# POWER.net
KiCad netlist of a schematic drawn in Altium Designer
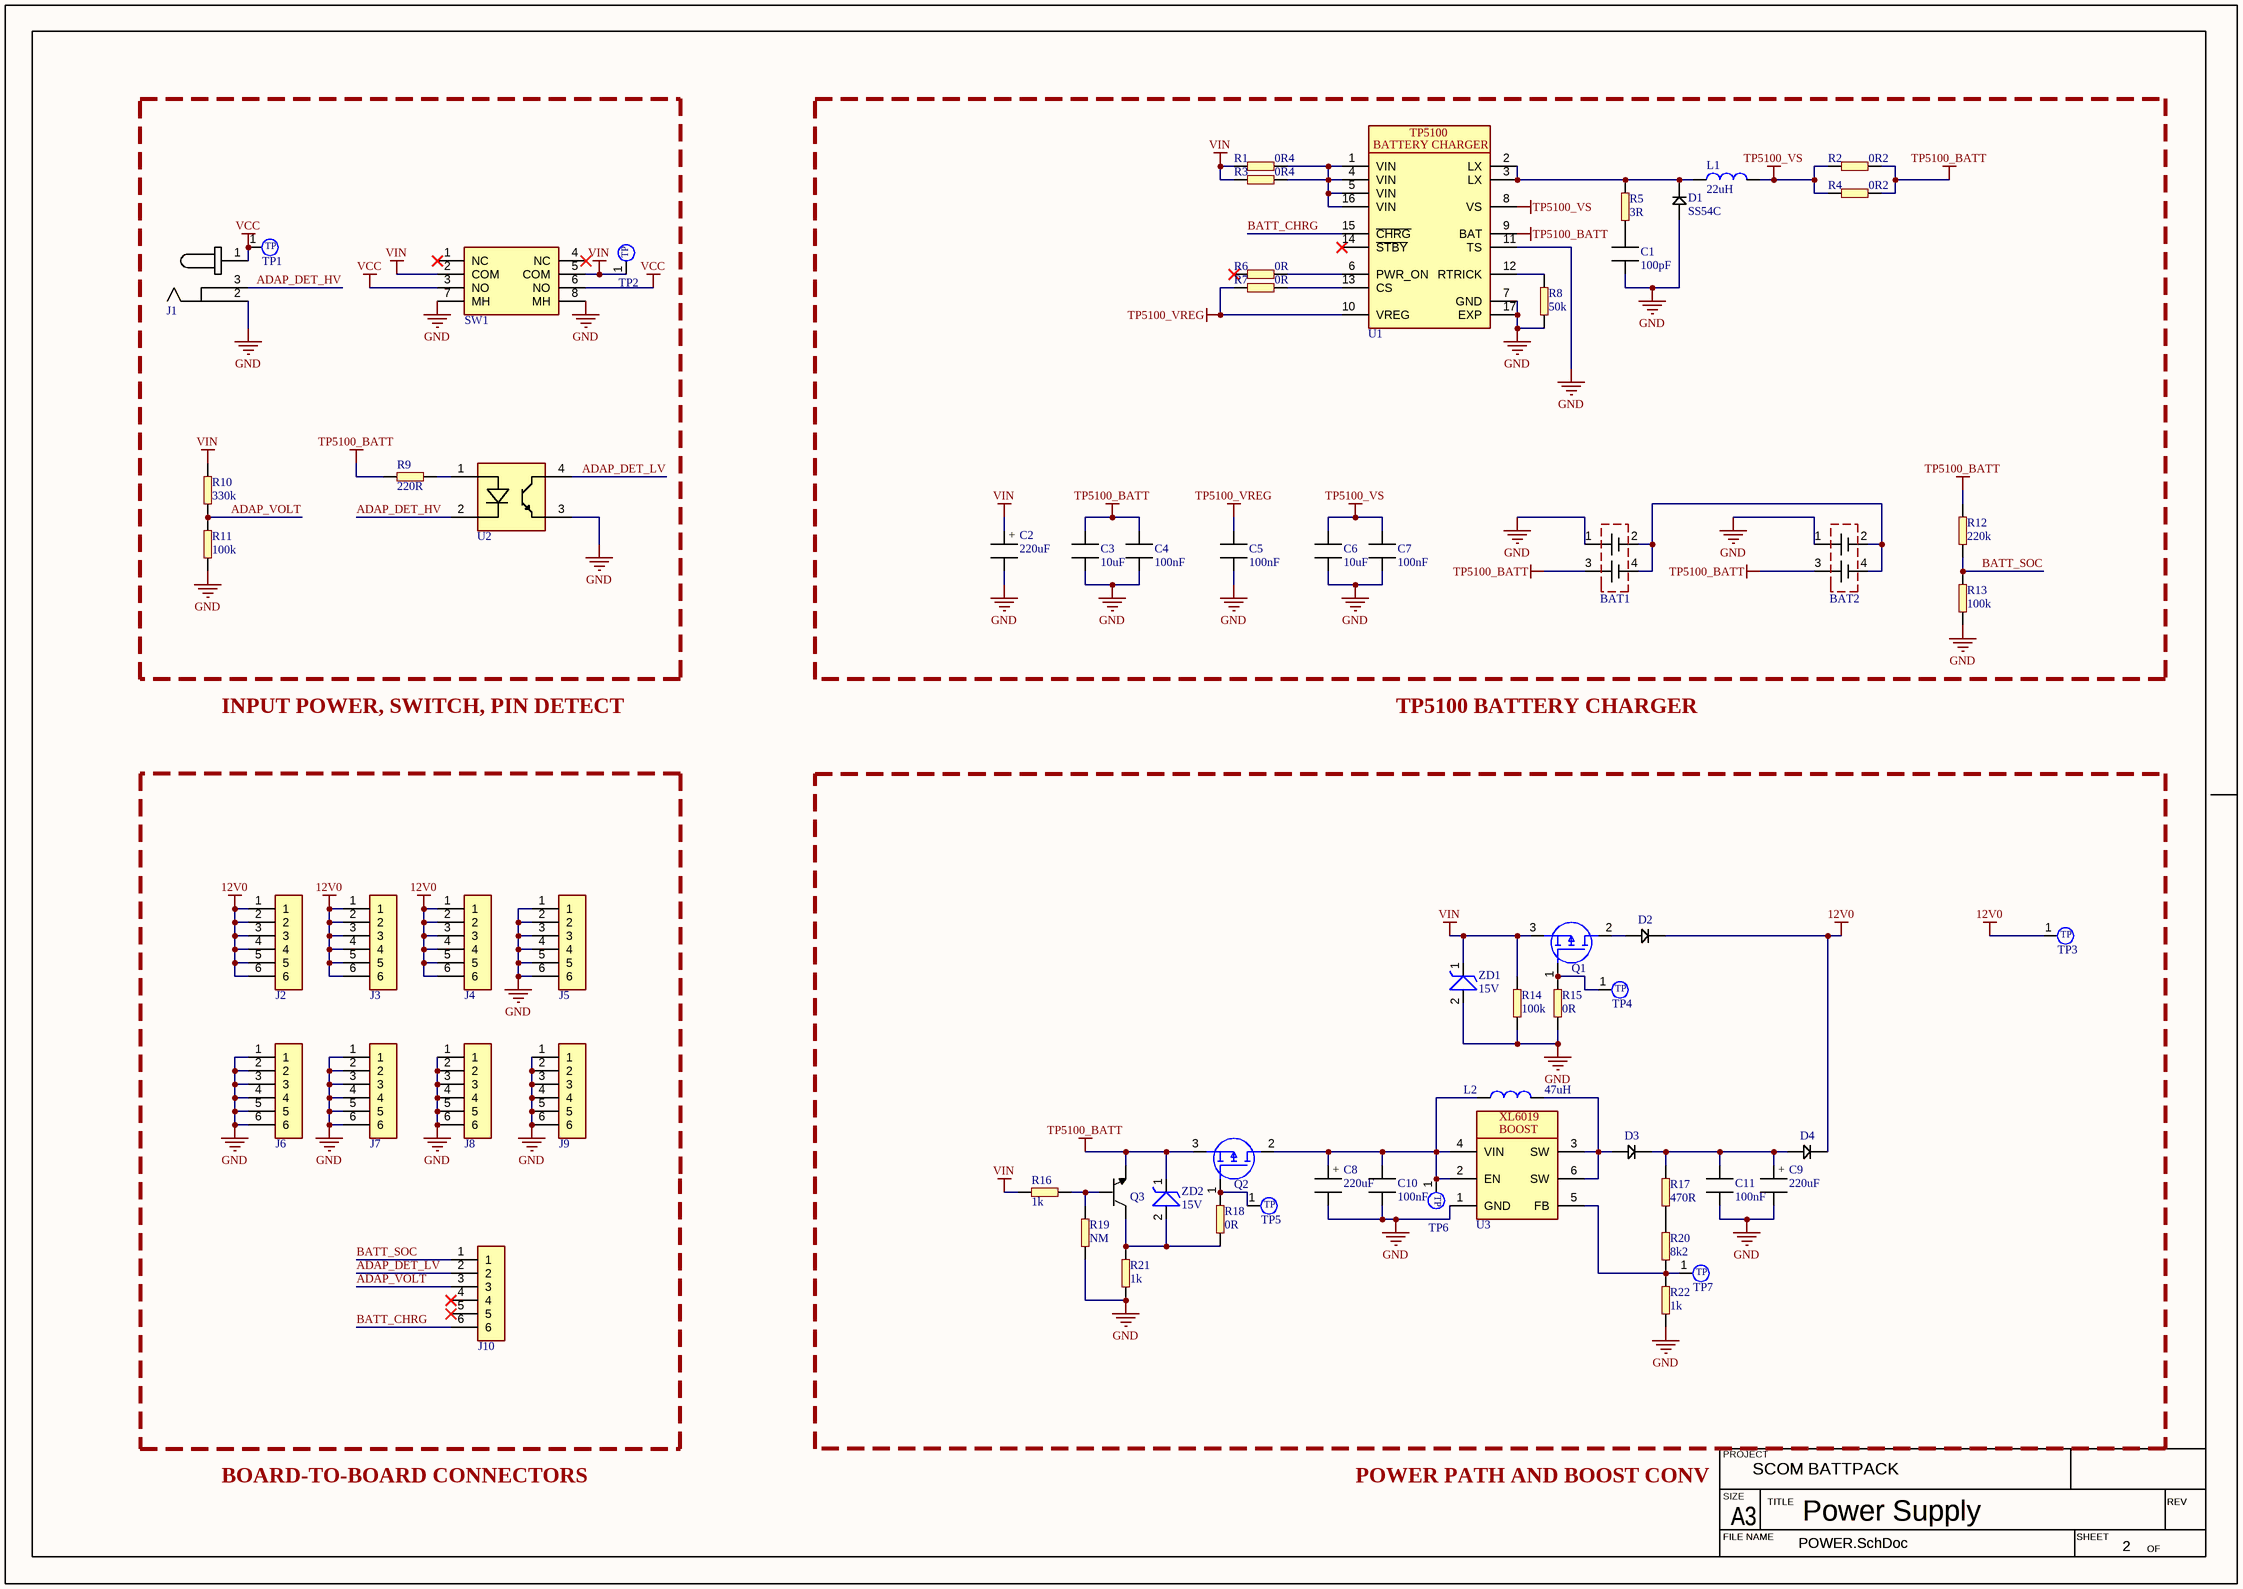
[diagram p0: POWER.SchDoc]

(export (version "E")
  (design (tool "Eeschema 10.0.6"))
  (components
    (comp (ref "BAT1")
      (value "BK-18650-PC4")
      (footprint "BK-18650-PC4")
      (description "BATT HOLDER 18650 2 CELL PC PIN")
      (libsource (lib "Connectors") (part "BK-18650-PC4"))
    )
    (comp (ref "BAT2")
      (value "BK-18650-PC4")
      (footprint "BK-18650-PC4")
      (description "BATT HOLDER 18650 2 CELL PC PIN")
      (libsource (lib "Connectors") (part "BK-18650-PC4"))
    )
    (comp (ref "C1")
      (value "100pF")
      (footprint "CAPC2012X13L")
      (description "Chip Capacitor, 2-Leads, Body 2.00x1.25mm, IPC High Density")
      (fields (field (name "Comment") "MLCC_0805"))
      (libsource (lib "Capacitor") (part "MLCC_0805"))
    )
    (comp (ref "C2")
      (value "220uF")
      (footprint "CAP_6.3_7.7")
      (description "Electrolytic Capacitor SMD 6.3x7.7")
      (fields (field (name "Comment") "ERP_102-2"))
      (libsource (lib "ElectrolyticCapacitor") (part "CAP_6.3_7.7"))
    )
    (comp (ref "C3")
      (value "10uF")
      (footprint "CAPC2012X13L")
      (description "Chip Capacitor, 2-Leads, Body 2.00x1.25mm, IPC High Density")
      (fields (field (name "Comment") "MLCC_0805"))
      (libsource (lib "Capacitor") (part "MLCC_0805"))
    )
    (comp (ref "C4")
      (value "100nF")
      (footprint "CAPC2012X13L")
      (description "Chip Capacitor, 2-Leads, Body 2.00x1.25mm, IPC High Density")
      (fields (field (name "Comment") "MLCC_0805"))
      (libsource (lib "Capacitor") (part "MLCC_0805"))
    )
    (comp (ref "C5")
      (value "100nF")
      (footprint "CAPC2012X13L")
      (description "Chip Capacitor, 2-Leads, Body 2.00x1.25mm, IPC High Density")
      (fields (field (name "Comment") "MLCC_0805"))
      (libsource (lib "Capacitor") (part "MLCC_0805"))
    )
    (comp (ref "C6")
      (value "10uF")
      (footprint "CAPC2012X13L")
      (description "Chip Capacitor, 2-Leads, Body 2.00x1.25mm, IPC High Density")
      (fields (field (name "Comment") "MLCC_0805"))
      (libsource (lib "Capacitor") (part "MLCC_0805"))
    )
    (comp (ref "C7")
      (value "100nF")
      (footprint "CAPC2012X13L")
      (description "Chip Capacitor, 2-Leads, Body 2.00x1.25mm, IPC High Density")
      (fields (field (name "Comment") "MLCC_0805"))
      (libsource (lib "Capacitor") (part "MLCC_0805"))
    )
    (comp (ref "C8")
      (value "220uF")
      (footprint "CAP_6.3_7.7")
      (description "Electrolytic Capacitor SMD 6.3x7.7")
      (fields (field (name "Comment") "ERP_102-2"))
      (libsource (lib "ElectrolyticCapacitor") (part "CAP_6.3_7.7"))
    )
    (comp (ref "C9")
      (value "220uF")
      (footprint "CAP_6.3_7.7")
      (description "Electrolytic Capacitor SMD 6.3x7.7")
      (fields (field (name "Comment") "ERP_102-2"))
      (libsource (lib "ElectrolyticCapacitor") (part "CAP_6.3_7.7"))
    )
    (comp (ref "C10")
      (value "100nF")
      (footprint "CAPC2012X13L")
      (description "Chip Capacitor, 2-Leads, Body 2.00x1.25mm, IPC High Density")
      (fields (field (name "Comment") "MLCC_0805"))
      (libsource (lib "Capacitor") (part "MLCC_0805"))
    )
    (comp (ref "C11")
      (value "100nF")
      (footprint "CAPC2012X13L")
      (description "Chip Capacitor, 2-Leads, Body 2.00x1.25mm, IPC High Density")
      (fields (field (name "Comment") "MLCC_0805"))
      (libsource (lib "Capacitor") (part "MLCC_0805"))
    )
    (comp (ref "D1")
      (value "SS54C")
      (footprint "DIOM6959X26L")
      (fields (field (name "Comment") "ERP_104-3"))
      (libsource (lib "Schottky") (part "SS54"))
    )
    (comp (ref "D2")
      (value "ERP_104-3")
      (footprint "DIOM6959X26L")
      (libsource (lib "Schottky") (part "SS54"))
    )
    (comp (ref "D3")
      (value "ERP_104-3")
      (footprint "DIOM6959X26L")
      (libsource (lib "Schottky") (part "SS54"))
    )
    (comp (ref "D4")
      (value "ERP_104-3")
      (footprint "DIOM6959X26L")
      (libsource (lib "Schottky") (part "SS54"))
    )
    (comp (ref "J1")
      (value "KLDX-0202-AC")
      (footprint "KLDX-0202-AC")
      (description "CONN PWR JACK 2X5.5MM KINKED PIN")
      (libsource (lib "Connectors") (part "KLDX-0202-AC"))
    )
    (comp (ref "J2")
      (value "ERP_148-2")
      (footprint "6PX1R_F")
      (description "6PX1R Female Header")
      (libsource (lib "PinHeader") (part "6PX1R_F"))
    )
    (comp (ref "J3")
      (value "ERP_148-2")
      (footprint "6PX1R_F")
      (description "6PX1R Female Header")
      (libsource (lib "PinHeader") (part "6PX1R_F"))
    )
    (comp (ref "J4")
      (value "ERP_148-2")
      (footprint "6PX1R_F")
      (description "6PX1R Female Header")
      (libsource (lib "PinHeader") (part "6PX1R_F"))
    )
    (comp (ref "J5")
      (value "ERP_148-2")
      (footprint "6PX1R_F")
      (description "6PX1R Female Header")
      (libsource (lib "PinHeader") (part "6PX1R_F"))
    )
    (comp (ref "J6")
      (value "ERP_148-2")
      (footprint "6PX1R_F")
      (description "6PX1R Female Header")
      (libsource (lib "PinHeader") (part "6PX1R_F"))
    )
    (comp (ref "J7")
      (value "ERP_148-2")
      (footprint "6PX1R_F")
      (description "6PX1R Female Header")
      (libsource (lib "PinHeader") (part "6PX1R_F"))
    )
    (comp (ref "J8")
      (value "ERP_148-2")
      (footprint "6PX1R_F")
      (description "6PX1R Female Header")
      (libsource (lib "PinHeader") (part "6PX1R_F"))
    )
    (comp (ref "J9")
      (value "ERP_148-2")
      (footprint "6PX1R_F")
      (description "6PX1R Female Header")
      (libsource (lib "PinHeader") (part "6PX1R_F"))
    )
    (comp (ref "J10")
      (value "ERP_148-2")
      (footprint "6PX1R_F")
      (description "6PX1R Female Header")
      (libsource (lib "PinHeader") (part "6PX1R_F"))
    )
    (comp (ref "L1")
      (value "22uH")
      (footprint "IND_1212")
      (description "IND_1212")
      (libsource (lib "Inductor") (part "IND_1212"))
    )
    (comp (ref "L2")
      (value "47uH")
      (footprint "IND_1212")
      (description "IND_1212")
      (libsource (lib "Inductor") (part "IND_1212"))
    )
    (comp (ref "Q1")
      (value "IRFR5305TRPBF")
      (footprint "DPAK229P991X239-3M")
      (description "P Channel MOSFET -55V HEXFET 65mOhms 42nC TO-252-3")
      (libsource (lib "MOSFET") (part "IRFR5305TRPBF"))
    )
    (comp (ref "Q2")
      (value "IRFR5305TRPBF")
      (footprint "DPAK229P991X239-3M")
      (description "P Channel MOSFET -55V HEXFET 65mOhms 42nC TO-252-3")
      (libsource (lib "MOSFET") (part "IRFR5305TRPBF"))
    )
    (comp (ref "Q3")
      (value "ERP_105-1")
      (footprint "MMBT2222")
      (description "MMBT2222A")
      (libsource (lib "BJT") (part "MMBT2222"))
    )
    (comp (ref "R1")
      (value "0R4")
      (footprint "RESC3116X06M")
      (description "RES_1206")
      (libsource (lib "Resistor") (part "RES_1206"))
    )
    (comp (ref "R2")
      (value "0R2")
      (footprint "RESC3116X06M")
      (description "RES_1206")
      (libsource (lib "Resistor") (part "RES_1206"))
    )
    (comp (ref "R3")
      (value "0R4")
      (footprint "RESC3116X06M")
      (description "RES_1206")
      (libsource (lib "Resistor") (part "RES_1206"))
    )
    (comp (ref "R4")
      (value "0R2")
      (footprint "RESC3116X06M")
      (description "RES_1206")
      (libsource (lib "Resistor") (part "RES_1206"))
    )
    (comp (ref "R5")
      (value "3R")
      (footprint "RES_0603")
      (description "RES_0603")
      (fields (field (name "Comment") "ERP_101-1"))
      (libsource (lib "") (part "RES_0603_2"))
    )
    (comp (ref "R6")
      (value "0R")
      (footprint "RES_0603")
      (description "RES_0603")
      (fields (field (name "Comment") "ERP_101-1"))
      (libsource (lib "") (part "RES_0603_1"))
    )
    (comp (ref "R7")
      (value "0R")
      (footprint "RES_0603")
      (description "RES_0603")
      (fields (field (name "Comment") "ERP_101-1"))
      (libsource (lib "") (part "RES_0603_1"))
    )
    (comp (ref "R8")
      (value "50k")
      (footprint "RES_0603")
      (description "RES_0603")
      (fields (field (name "Comment") "ERP_101-1"))
      (libsource (lib "") (part "RES_0603_2"))
    )
    (comp (ref "R9")
      (value "220R")
      (footprint "RES_0603")
      (description "RES_0603")
      (fields (field (name "Comment") "ERP_101-1"))
      (libsource (lib "") (part "RES_0603_1"))
    )
    (comp (ref "R10")
      (value "330k")
      (footprint "RES_0603")
      (description "RES_0603")
      (fields (field (name "Comment") "ERP_101-1"))
      (libsource (lib "") (part "RES_0603_2"))
    )
    (comp (ref "R11")
      (value "100k")
      (footprint "RES_0603")
      (description "RES_0603")
      (fields (field (name "Comment") "ERP_101-1"))
      (libsource (lib "Resistor") (part "RES_0603"))
    )
    (comp (ref "R12")
      (value "220k")
      (footprint "RES_0603")
      (description "RES_0603")
      (fields (field (name "Comment") "ERP_101-1"))
      (libsource (lib "") (part "RES_0603_2"))
    )
    (comp (ref "R13")
      (value "100k")
      (footprint "RES_0603")
      (description "RES_0603")
      (fields (field (name "Comment") "ERP_101-1"))
      (libsource (lib "") (part "RES_0603_2"))
    )
    (comp (ref "R14")
      (value "100k")
      (footprint "RES_0603")
      (description "RES_0603")
      (fields (field (name "Comment") "ERP_101-1"))
      (libsource (lib "") (part "RES_0603_2"))
    )
    (comp (ref "R15")
      (value "0R")
      (footprint "RES_0603")
      (description "RES_0603")
      (fields (field (name "Comment") "ERP_101-1"))
      (libsource (lib "") (part "RES_0603_2"))
    )
    (comp (ref "R16")
      (value "1k")
      (footprint "RES_0603")
      (description "RES_0603")
      (fields (field (name "Comment") "ERP_101-1"))
      (libsource (lib "") (part "RES_0603_3"))
    )
    (comp (ref "R17")
      (value "470R")
      (footprint "RES_0603")
      (description "RES_0603")
      (fields (field (name "Comment") "ERP_101-1"))
      (libsource (lib "Resistor") (part "RES_0603"))
    )
    (comp (ref "R18")
      (value "0R")
      (footprint "RES_0603")
      (description "RES_0603")
      (fields (field (name "Comment") "ERP_101-1"))
      (libsource (lib "") (part "RES_0603_2"))
    )
    (comp (ref "R19")
      (value "NM")
      (footprint "RES_0603")
      (description "RES_0603")
      (fields (field (name "Comment") "ERP_101-1"))
      (libsource (lib "Resistor") (part "RES_0603"))
    )
    (comp (ref "R20")
      (value "8k2")
      (footprint "RES_0603")
      (description "RES_0603")
      (fields (field (name "Comment") "ERP_101-1"))
      (libsource (lib "Resistor") (part "RES_0603"))
    )
    (comp (ref "R21")
      (value "1k")
      (footprint "RES_0603")
      (description "RES_0603")
      (fields (field (name "Comment") "ERP_101-1"))
      (libsource (lib "Resistor") (part "RES_0603"))
    )
    (comp (ref "R22")
      (value "1k")
      (footprint "RES_0603")
      (description "RES_0603")
      (fields (field (name "Comment") "ERP_101-1"))
      (libsource (lib "Resistor") (part "RES_0603"))
    )
    (comp (ref "SW1")
      (value "ERP_110-4")
      (footprint "PBH2U")
      (description "Pushbutton Switch DPDT Standard Through Hole, Right Angle")
      (libsource (lib "Switch") (part "PBH2U"))
    )
    (comp (ref "TP1") (value "TP_1MM") (footprint "TP_1MM") (libsource (lib "Jumper") (part "TP_1MM")))
    (comp (ref "TP2") (value "TP_1MM") (footprint "TP_1MM") (libsource (lib "Jumper") (part "TP_1MM")))
    (comp (ref "TP3") (value "TP_1MM") (footprint "TP_1MM") (libsource (lib "Jumper") (part "TP_1MM")))
    (comp (ref "TP4") (value "TP_1MM") (footprint "TP_1MM") (libsource (lib "Jumper") (part "TP_1MM")))
    (comp (ref "TP5") (value "TP_1MM") (footprint "TP_1MM") (libsource (lib "Jumper") (part "TP_1MM")))
    (comp (ref "TP6") (value "TP_1MM") (footprint "TP_1MM") (libsource (lib "Jumper") (part "TP_1MM")))
    (comp (ref "TP7") (value "TP_1MM") (footprint "TP_1MM") (libsource (lib "Jumper") (part "TP_1MM")))
    (comp (ref "U1")
      (value "TP5100")
      (footprint "QFN65P400X400X90_HS-17M")
      (description "Switching-buck type (double 8.4V / single 4.2V) lithium battery charging management chip")
      (libsource (lib "BatteryCharger") (part "TP5100"))
    )
    (comp (ref "U2")
      (value "FOD817A3SD")
      (footprint "FOD817A3SD")
      (description "OPTOISOLATOR 5KV TRANSISTOR 4SMD")
      (libsource (lib "Optocoupler") (part "FOD817A3SD"))
    )
    (comp (ref "U3")
      (value "XL6019")
      (footprint "DPAK171P1524X483-6M")
      (description "5A 180KHz 32V Boost DC to DC Converter")
      (libsource (lib "DCDC_Switcher") (part "XL6019"))
    )
    (comp (ref "ZD1")
      (value "15V")
      (footprint "SOD323")
      (description "Zener SOD-323 0.3W")
      (fields (field (name "Comment") "MM3Z"))
      (libsource (lib "Zener") (part "MM3Z"))
    )
    (comp (ref "ZD2")
      (value "15V")
      (footprint "SOD323")
      (description "Zener SOD-323 0.3W")
      (fields (field (name "Comment") "MM3Z"))
      (libsource (lib "Zener") (part "MM3Z"))
    )
  )
  (nets
    (net (code "1") (name "/ADAP_DET_HV") (class "Default")
      (node (ref "J1") (pin "3") (pinfunction "3_3") (pintype "passive"))
      (node (ref "U2") (pin "2") (pinfunction "CATHODE_2") (pintype "passive"))
    )
    (net (code "2") (name "/ADAP_DET_LV") (class "Default")
      (node (ref "J10") (pin "2") (pinfunction "2_2") (pintype "passive"))
      (node (ref "U2") (pin "4") (pinfunction "COLLECTOR_4") (pintype "passive"))
    )
    (net (code "3") (name "/ADAP_VOLT") (class "Default")
      (node (ref "J10") (pin "3") (pinfunction "3_3") (pintype "passive"))
      (node (ref "R10") (pin "1") (pinfunction "1_1") (pintype "passive"))
      (node (ref "R11") (pin "1") (pinfunction "1_1") (pintype "passive"))
    )
    (net (code "4") (name "/BATT_CHRG") (class "Default")
      (node (ref "J10") (pin "6") (pinfunction "6_6") (pintype "passive"))
      (node (ref "U1") (pin "15") (pinfunction "~{CHRG}_15") (pintype "passive"))
    )
    (net (code "5") (name "/BATT_SOC") (class "Default")
      (node (ref "J10") (pin "1") (pinfunction "1_1") (pintype "passive"))
      (node (ref "R12") (pin "1") (pinfunction "1_1") (pintype "passive"))
      (node (ref "R13") (pin "2") (pinfunction "2_2") (pintype "passive"))
    )
    (net (code "6") (name "12V0") (class "Default")
      (node (ref "D2") (pin "1") (pinfunction "C_1") (pintype "passive"))
      (node (ref "D4") (pin "1") (pinfunction "C_1") (pintype "passive"))
      (node (ref "J2") (pin "1") (pinfunction "1_1") (pintype "passive"))
      (node (ref "J2") (pin "2") (pinfunction "2_2") (pintype "passive"))
      (node (ref "J2") (pin "3") (pinfunction "3_3") (pintype "passive"))
      (node (ref "J2") (pin "4") (pinfunction "4_4") (pintype "passive"))
      (node (ref "J2") (pin "5") (pinfunction "5_5") (pintype "passive"))
      (node (ref "J2") (pin "6") (pinfunction "6_6") (pintype "passive"))
      (node (ref "J3") (pin "1") (pinfunction "1_1") (pintype "passive"))
      (node (ref "J3") (pin "2") (pinfunction "2_2") (pintype "passive"))
      (node (ref "J3") (pin "3") (pinfunction "3_3") (pintype "passive"))
      (node (ref "J3") (pin "4") (pinfunction "4_4") (pintype "passive"))
      (node (ref "J3") (pin "5") (pinfunction "5_5") (pintype "passive"))
      (node (ref "J3") (pin "6") (pinfunction "6_6") (pintype "passive"))
      (node (ref "J4") (pin "1") (pinfunction "1_1") (pintype "passive"))
      (node (ref "J4") (pin "2") (pinfunction "2_2") (pintype "passive"))
      (node (ref "J4") (pin "3") (pinfunction "3_3") (pintype "passive"))
      (node (ref "J4") (pin "4") (pinfunction "4_4") (pintype "passive"))
      (node (ref "J4") (pin "5") (pinfunction "5_5") (pintype "passive"))
      (node (ref "J4") (pin "6") (pinfunction "6_6") (pintype "passive"))
      (node (ref "TP3") (pin "1") (pinfunction "1_1") (pintype "passive"))
    )
    (net (code "7") (name "GND") (class "Default")
      (node (ref "BAT1") (pin "1") (pinfunction "+_1") (pintype "passive"))
      (node (ref "BAT2") (pin "1") (pinfunction "+_1") (pintype "passive"))
      (node (ref "C1") (pin "2") (pinfunction "2_2") (pintype "passive"))
      (node (ref "C10") (pin "2") (pinfunction "2_2") (pintype "passive"))
      (node (ref "C11") (pin "2") (pinfunction "2_2") (pintype "passive"))
      (node (ref "C2") (pin "2") (pinfunction "2_2") (pintype "passive"))
      (node (ref "C3") (pin "2") (pinfunction "2_2") (pintype "passive"))
      (node (ref "C4") (pin "2") (pinfunction "2_2") (pintype "passive"))
      (node (ref "C5") (pin "2") (pinfunction "2_2") (pintype "passive"))
      (node (ref "C6") (pin "2") (pinfunction "2_2") (pintype "passive"))
      (node (ref "C7") (pin "2") (pinfunction "2_2") (pintype "passive"))
      (node (ref "C8") (pin "2") (pinfunction "2_2") (pintype "passive"))
      (node (ref "C9") (pin "2") (pinfunction "2_2") (pintype "passive"))
      (node (ref "D1") (pin "2") (pinfunction "A_2") (pintype "passive"))
      (node (ref "J1") (pin "2") (pinfunction "2_2") (pintype "passive"))
      (node (ref "J5") (pin "1") (pinfunction "1_1") (pintype "passive"))
      (node (ref "J5") (pin "2") (pinfunction "2_2") (pintype "passive"))
      (node (ref "J5") (pin "3") (pinfunction "3_3") (pintype "passive"))
      (node (ref "J5") (pin "4") (pinfunction "4_4") (pintype "passive"))
      (node (ref "J5") (pin "5") (pinfunction "5_5") (pintype "passive"))
      (node (ref "J5") (pin "6") (pinfunction "6_6") (pintype "passive"))
      (node (ref "J6") (pin "1") (pinfunction "1_1") (pintype "passive"))
      (node (ref "J6") (pin "2") (pinfunction "2_2") (pintype "passive"))
      (node (ref "J6") (pin "3") (pinfunction "3_3") (pintype "passive"))
      (node (ref "J6") (pin "4") (pinfunction "4_4") (pintype "passive"))
      (node (ref "J6") (pin "5") (pinfunction "5_5") (pintype "passive"))
      (node (ref "J6") (pin "6") (pinfunction "6_6") (pintype "passive"))
      (node (ref "J7") (pin "1") (pinfunction "1_1") (pintype "passive"))
      (node (ref "J7") (pin "2") (pinfunction "2_2") (pintype "passive"))
      (node (ref "J7") (pin "3") (pinfunction "3_3") (pintype "passive"))
      (node (ref "J7") (pin "4") (pinfunction "4_4") (pintype "passive"))
      (node (ref "J7") (pin "5") (pinfunction "5_5") (pintype "passive"))
      (node (ref "J7") (pin "6") (pinfunction "6_6") (pintype "passive"))
      (node (ref "J8") (pin "1") (pinfunction "1_1") (pintype "passive"))
      (node (ref "J8") (pin "2") (pinfunction "2_2") (pintype "passive"))
      (node (ref "J8") (pin "3") (pinfunction "3_3") (pintype "passive"))
      (node (ref "J8") (pin "4") (pinfunction "4_4") (pintype "passive"))
      (node (ref "J8") (pin "5") (pinfunction "5_5") (pintype "passive"))
      (node (ref "J8") (pin "6") (pinfunction "6_6") (pintype "passive"))
      (node (ref "J9") (pin "1") (pinfunction "1_1") (pintype "passive"))
      (node (ref "J9") (pin "2") (pinfunction "2_2") (pintype "passive"))
      (node (ref "J9") (pin "3") (pinfunction "3_3") (pintype "passive"))
      (node (ref "J9") (pin "4") (pinfunction "4_4") (pintype "passive"))
      (node (ref "J9") (pin "5") (pinfunction "5_5") (pintype "passive"))
      (node (ref "J9") (pin "6") (pinfunction "6_6") (pintype "passive"))
      (node (ref "R11") (pin "2") (pinfunction "2_2") (pintype "passive"))
      (node (ref "R13") (pin "1") (pinfunction "1_1") (pintype "passive"))
      (node (ref "R14") (pin "1") (pinfunction "1_1") (pintype "passive"))
      (node (ref "R15") (pin "1") (pinfunction "1_1") (pintype "passive"))
      (node (ref "R19") (pin "2") (pinfunction "2_2") (pintype "passive"))
      (node (ref "R21") (pin "2") (pinfunction "2_2") (pintype "passive"))
      (node (ref "R22") (pin "2") (pinfunction "2_2") (pintype "passive"))
      (node (ref "R8") (pin "1") (pinfunction "1_1") (pintype "passive"))
      (node (ref "SW1") (pin "7") (pinfunction "MH_7") (pintype "passive"))
      (node (ref "SW1") (pin "8") (pinfunction "MH_8") (pintype "passive"))
      (node (ref "U1") (pin "11") (pinfunction "TS_11") (pintype "passive"))
      (node (ref "U1") (pin "17") (pinfunction "EXP_17") (pintype "passive"))
      (node (ref "U1") (pin "7") (pinfunction "GND_7") (pintype "passive"))
      (node (ref "U2") (pin "3") (pinfunction "EMITTER_3") (pintype "passive"))
      (node (ref "U3") (pin "1") (pinfunction "GND_1") (pintype "passive"))
      (node (ref "ZD1") (pin "2") (pinfunction "A_2") (pintype "passive"))
    )
    (net (code "8") (name "Net-(BAT1---Pad2)") (class "Default")
      (node (ref "BAT1") (pin "2") (pinfunction "-_2") (pintype "passive"))
      (node (ref "BAT1") (pin "4") (pinfunction "-_4") (pintype "passive"))
      (node (ref "BAT2") (pin "2") (pinfunction "-_2") (pintype "passive"))
      (node (ref "BAT2") (pin "4") (pinfunction "-_4") (pintype "passive"))
    )
    (net (code "9") (name "Net-(C1-Pad1)") (class "Default")
      (node (ref "C1") (pin "1") (pinfunction "1_1") (pintype "passive"))
      (node (ref "R5") (pin "1") (pinfunction "1_1") (pintype "passive"))
    )
    (net (code "10") (name "Net-(D1-C)") (class "Default")
      (node (ref "D1") (pin "1") (pinfunction "C_1") (pintype "passive"))
      (node (ref "L1") (pin "1") (pinfunction "1_1") (pintype "passive"))
      (node (ref "R5") (pin "2") (pinfunction "2_2") (pintype "passive"))
      (node (ref "U1") (pin "2") (pinfunction "LX_2") (pintype "passive"))
      (node (ref "U1") (pin "3") (pinfunction "LX_3") (pintype "passive"))
    )
    (net (code "11") (name "Net-(D2-A)") (class "Default")
      (node (ref "D2") (pin "2") (pinfunction "A_2") (pintype "passive"))
      (node (ref "Q1") (pin "2") (pinfunction "D_2") (pintype "passive"))
    )
    (net (code "12") (name "Net-(D3-A)") (class "Default")
      (node (ref "D3") (pin "2") (pinfunction "A_2") (pintype "passive"))
      (node (ref "L2") (pin "2") (pinfunction "2_2") (pintype "passive"))
      (node (ref "U3") (pin "3") (pinfunction "SW_3") (pintype "passive"))
      (node (ref "U3") (pin "6") (pinfunction "SW_6") (pintype "passive"))
    )
    (net (code "13") (name "Net-(D3-C)") (class "Default")
      (node (ref "C11") (pin "1") (pinfunction "1_1") (pintype "passive"))
      (node (ref "C9") (pin "1") (pinfunction "1_1") (pintype "passive"))
      (node (ref "D3") (pin "1") (pinfunction "C_1") (pintype "passive"))
      (node (ref "D4") (pin "2") (pinfunction "A_2") (pintype "passive"))
      (node (ref "R17") (pin "1") (pinfunction "1_1") (pintype "passive"))
    )
    (net (code "14") (name "Net-(Q1-G)") (class "Default")
      (node (ref "Q1") (pin "1") (pinfunction "G_1") (pintype "passive"))
      (node (ref "R15") (pin "2") (pinfunction "2_2") (pintype "passive"))
      (node (ref "TP4") (pin "1") (pinfunction "1_1") (pintype "passive"))
    )
    (net (code "15") (name "Net-(Q2-D)") (class "Default")
      (node (ref "C10") (pin "1") (pinfunction "1_1") (pintype "passive"))
      (node (ref "C8") (pin "1") (pinfunction "1_1") (pintype "passive"))
      (node (ref "L2") (pin "1") (pinfunction "1_1") (pintype "passive"))
      (node (ref "Q2") (pin "2") (pinfunction "D_2") (pintype "passive"))
      (node (ref "TP6") (pin "1") (pinfunction "1_1") (pintype "passive"))
      (node (ref "U3") (pin "2") (pinfunction "EN_2") (pintype "passive"))
      (node (ref "U3") (pin "4") (pinfunction "VIN_4") (pintype "passive"))
    )
    (net (code "16") (name "Net-(Q2-G)") (class "Default")
      (node (ref "Q2") (pin "1") (pinfunction "G_1") (pintype "passive"))
      (node (ref "R18") (pin "2") (pinfunction "2_2") (pintype "passive"))
      (node (ref "TP5") (pin "1") (pinfunction "1_1") (pintype "passive"))
    )
    (net (code "17") (name "Net-(Q3-Pad1)") (class "Default")
      (node (ref "Q3") (pin "1") (pinfunction "1_1") (pintype "passive"))
      (node (ref "R16") (pin "1") (pinfunction "1_1") (pintype "passive"))
      (node (ref "R19") (pin "1") (pinfunction "1_1") (pintype "passive"))
    )
    (net (code "18") (name "Net-(R1-Pad1)") (class "Default")
      (node (ref "R1") (pin "1") (pinfunction "1_1") (pintype "passive"))
      (node (ref "R3") (pin "1") (pinfunction "1_1") (pintype "passive"))
      (node (ref "U1") (pin "1") (pinfunction "VIN_1") (pintype "passive"))
      (node (ref "U1") (pin "16") (pinfunction "VIN_16") (pintype "passive"))
      (node (ref "U1") (pin "4") (pinfunction "VIN_4") (pintype "passive"))
      (node (ref "U1") (pin "5") (pinfunction "VIN_5") (pintype "passive"))
    )
    (net (code "19") (name "Net-(R17-Pad2)") (class "Default")
      (node (ref "R17") (pin "2") (pinfunction "2_2") (pintype "passive"))
      (node (ref "R20") (pin "1") (pinfunction "1_1") (pintype "passive"))
    )
    (net (code "20") (name "Net-(U1-CS)") (class "Default")
      (node (ref "R7") (pin "2") (pinfunction "2_2") (pintype "passive"))
      (node (ref "U1") (pin "13") (pinfunction "CS_13") (pintype "passive"))
    )
    (net (code "21") (name "Net-(U1-PWR_ON)") (class "Default")
      (node (ref "R6") (pin "2") (pinfunction "2_2") (pintype "passive"))
      (node (ref "U1") (pin "6") (pinfunction "PWR_ON_6") (pintype "passive"))
    )
    (net (code "22") (name "Net-(U1-RTRICK)") (class "Default")
      (node (ref "R8") (pin "2") (pinfunction "2_2") (pintype "passive"))
      (node (ref "U1") (pin "12") (pinfunction "RTRICK_12") (pintype "passive"))
    )
    (net (code "23") (name "Net-(U2-ANODE)") (class "Default")
      (node (ref "R9") (pin "2") (pinfunction "2_2") (pintype "passive"))
      (node (ref "U2") (pin "1") (pinfunction "ANODE_1") (pintype "passive"))
    )
    (net (code "24") (name "Net-(U3-FB)") (class "Default")
      (node (ref "R20") (pin "2") (pinfunction "2_2") (pintype "passive"))
      (node (ref "R22") (pin "1") (pinfunction "1_1") (pintype "passive"))
      (node (ref "TP7") (pin "1") (pinfunction "1_1") (pintype "passive"))
      (node (ref "U3") (pin "5") (pinfunction "FB_5") (pintype "passive"))
    )
    (net (code "25") (name "Net-(ZD2-A)") (class "Default")
      (node (ref "Q3") (pin "3") (pinfunction "3_3") (pintype "passive"))
      (node (ref "R18") (pin "1") (pinfunction "1_1") (pintype "passive"))
      (node (ref "R21") (pin "1") (pinfunction "1_1") (pintype "passive"))
      (node (ref "ZD2") (pin "2") (pinfunction "A_2") (pintype "passive"))
    )
    (net (code "26") (name "TP5100_BATT") (class "Default")
      (node (ref "BAT1") (pin "3") (pinfunction "+_3") (pintype "passive"))
      (node (ref "BAT2") (pin "3") (pinfunction "+_3") (pintype "passive"))
      (node (ref "C3") (pin "1") (pinfunction "1_1") (pintype "passive"))
      (node (ref "C4") (pin "1") (pinfunction "1_1") (pintype "passive"))
      (node (ref "Q2") (pin "3") (pinfunction "S_3") (pintype "passive"))
      (node (ref "Q3") (pin "2") (pinfunction "2_2") (pintype "passive"))
      (node (ref "R12") (pin "2") (pinfunction "2_2") (pintype "passive"))
      (node (ref "R2") (pin "1") (pinfunction "1_1") (pintype "passive"))
      (node (ref "R4") (pin "1") (pinfunction "1_1") (pintype "passive"))
      (node (ref "R9") (pin "1") (pinfunction "1_1") (pintype "passive"))
      (node (ref "U1") (pin "9") (pinfunction "BAT_9") (pintype "passive"))
      (node (ref "ZD2") (pin "1") (pinfunction "K_1") (pintype "passive"))
    )
    (net (code "27") (name "TP5100_VREG") (class "Default")
      (node (ref "C5") (pin "1") (pinfunction "1_1") (pintype "passive"))
      (node (ref "R7") (pin "1") (pinfunction "1_1") (pintype "passive"))
      (node (ref "U1") (pin "10") (pinfunction "VREG_10") (pintype "passive"))
    )
    (net (code "28") (name "TP5100_VS") (class "Default")
      (node (ref "C6") (pin "1") (pinfunction "1_1") (pintype "passive"))
      (node (ref "C7") (pin "1") (pinfunction "1_1") (pintype "passive"))
      (node (ref "L1") (pin "2") (pinfunction "2_2") (pintype "passive"))
      (node (ref "R2") (pin "2") (pinfunction "2_2") (pintype "passive"))
      (node (ref "R4") (pin "2") (pinfunction "2_2") (pintype "passive"))
      (node (ref "U1") (pin "8") (pinfunction "VS_8") (pintype "passive"))
    )
    (net (code "29") (name "VCC") (class "Default")
      (node (ref "J1") (pin "1") (pinfunction "1_1") (pintype "passive"))
      (node (ref "SW1") (pin "3") (pinfunction "NO_3") (pintype "passive"))
      (node (ref "SW1") (pin "6") (pinfunction "NO_6") (pintype "passive"))
      (node (ref "TP1") (pin "1") (pinfunction "1_1") (pintype "passive"))
    )
    (net (code "30") (name "VIN") (class "Default")
      (node (ref "C2") (pin "1") (pinfunction "1_1") (pintype "passive"))
      (node (ref "Q1") (pin "3") (pinfunction "S_3") (pintype "passive"))
      (node (ref "R1") (pin "2") (pinfunction "2_2") (pintype "passive"))
      (node (ref "R10") (pin "2") (pinfunction "2_2") (pintype "passive"))
      (node (ref "R14") (pin "2") (pinfunction "2_2") (pintype "passive"))
      (node (ref "R16") (pin "2") (pinfunction "2_2") (pintype "passive"))
      (node (ref "R3") (pin "2") (pinfunction "2_2") (pintype "passive"))
      (node (ref "SW1") (pin "2") (pinfunction "COM_2") (pintype "passive"))
      (node (ref "SW1") (pin "5") (pinfunction "COM_5") (pintype "passive"))
      (node (ref "TP2") (pin "1") (pinfunction "1_1") (pintype "passive"))
      (node (ref "ZD1") (pin "1") (pinfunction "K_1") (pintype "passive"))
    )
    (net (code "31") (name "unconnected-(J10-Pad4)") (class "Default")
      (node (ref "J10") (pin "4") (pinfunction "4_4") (pintype "passive+no_connect"))
    )
    (net (code "32") (name "unconnected-(J10-Pad5)") (class "Default")
      (node (ref "J10") (pin "5") (pinfunction "5_5") (pintype "passive+no_connect"))
    )
    (net (code "33") (name "unconnected-(R6-Pad1)") (class "Default")
      (node (ref "R6") (pin "1") (pinfunction "1_1") (pintype "passive+no_connect"))
    )
    (net (code "34") (name "unconnected-(SW1-NC-Pad1)") (class "Default")
      (node (ref "SW1") (pin "1") (pinfunction "NC_1") (pintype "passive+no_connect"))
    )
    (net (code "35") (name "unconnected-(SW1-NC-Pad4)") (class "Default")
      (node (ref "SW1") (pin "4") (pinfunction "NC_4") (pintype "passive+no_connect"))
    )
    (net (code "36") (name "unconnected-(U1-~{STBY}-Pad14)") (class "Default")
      (node (ref "U1") (pin "14") (pinfunction "~{STBY}_14") (pintype "passive+no_connect"))
    )
  )
)
